# 5V2A_Flyback_converter_Schematic.net
KiCad netlist of a schematic drawn in Altium Designer
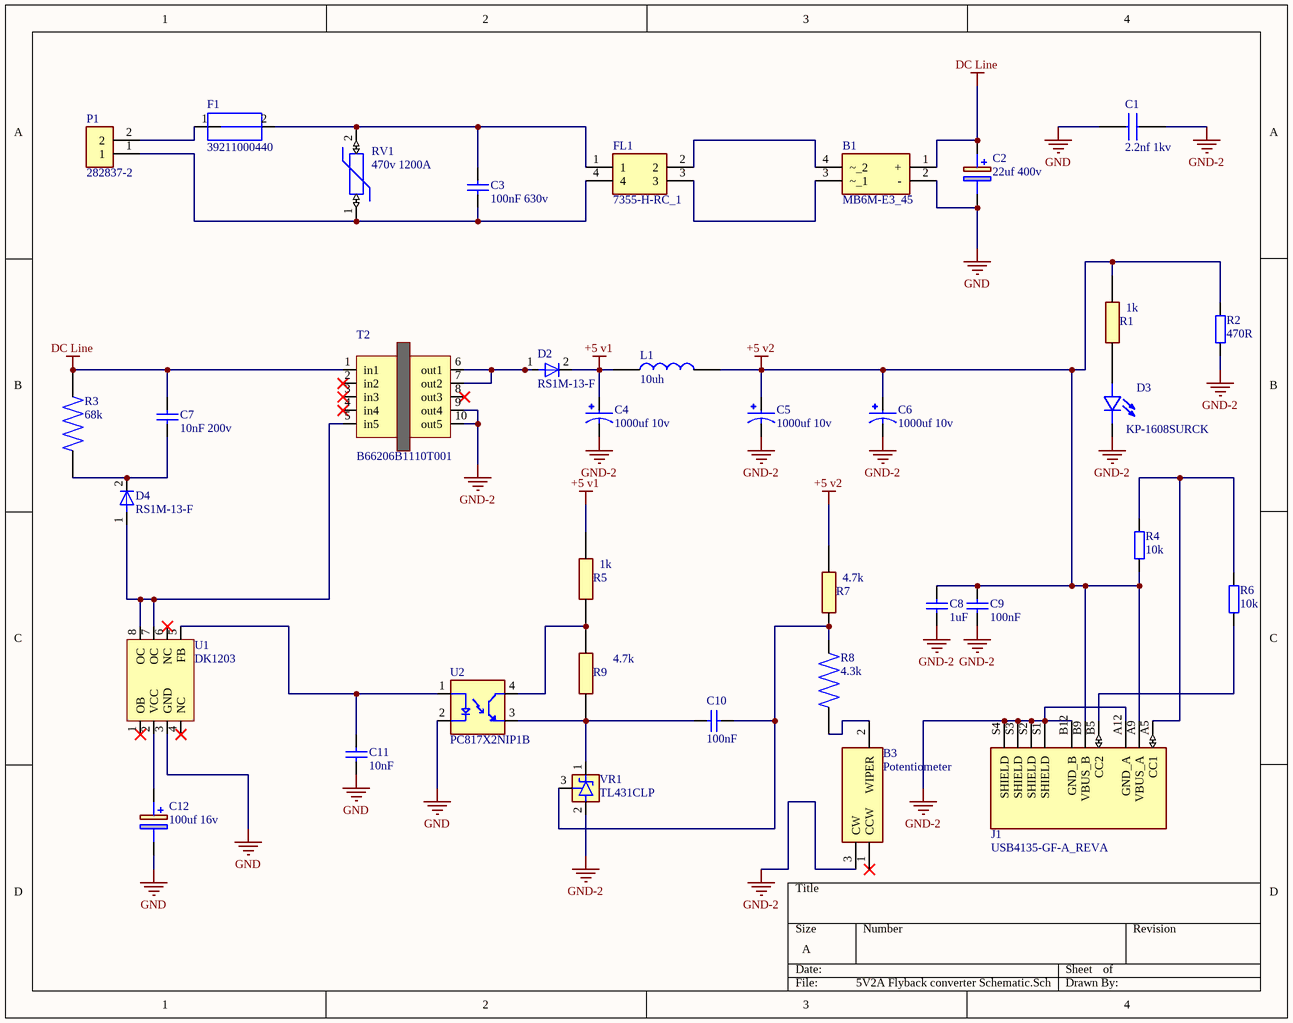
[diagram p0: 5V2A Flyback converter Schematic.SchDoc]

(export (version "E")
  (design (tool "Eeschema 10.0.6"))
  (components
    (comp (ref "B1")
      (value "MB6M-E3_45")
      (footprint "DIP508W74P254L469H270Q4N")
      (description "Diode Rectifier Bridge Single 600V 0.8A Vishay MB6M-E3/45, Bridge Rectifier, 0.8A 600V, 4-Pin MBM")
      (fields
        (field (name "MANUFACTURER_PART_NUMBER") "MB6M-E3/45")
        (field (name "MOUSER PART NUMBER") "625-MB6M-E3")
      )
      (libsource (lib "5V2A Flyback converter Schematic library") (part "MB6M-E3_45"))
    )
    (comp (ref "B3")
      (value "Potentiometer")
      (footprint "3296Y1504LF")
      (description "Trimmer Resistors - Through Hole 3/8\" 500Kohms Sealed Vertical Adjust")
      (fields
        (field (name "MANUFACTURER_PART_NUMBER") "3296Y-1-504LF")
        (field (name "MOUSER PART NUMBER") "652-3296Y-1-504LF")
      )
      (libsource (lib "5V2A Flyback converter Schematic library") (part "Potentiometer"))
    )
    (comp (ref "C1")
      (value "2.2nf 1kv")
      (footprint "CK45B3AD222KYNNA")
      (fields
        (field (name "MANUFACTURER_PART_NUMBER") "CK45-B3AD222KYNNA")
        (field (name "MOUSER PART NUMBER") "810-CK45-B3AD222NNA")
      )
      (libsource (lib "5V2A Flyback converter Schematic library") (part "2.2nf 1kv"))
    )
    (comp (ref "C2")
      (value "22uf 400v")
      (footprint "CAPPRD500W65D1250H2700")
      (description "Aluminium Electrolytic Capacitors - Radial Leaded Al Lytic Cap Radial NHG Series 105C")
      (fields
        (field (name "MANUFACTURER_PART_NUMBER") "ECA-2GHG220")
        (field (name "MOUSER PART NUMBER") "667-ECA-2GHG220")
      )
      (libsource (lib "5V2A Flyback converter Schematic library") (part "22uf"))
    )
    (comp (ref "C3")
      (value "100nF 630v")
      (footprint "WCAP-CSMH_1812_L4.5W3.2H2")
      (fields
        (field (name "MANUFACTURER PART NUMBER") "885342211006")
        (field (name "MANUFACTURER") "Wurth Elektronik")
      )
      (libsource (lib "885342006001_Altium_WCAP-CSMH_rev24a") (part "885342211006"))
    )
    (comp (ref "C4")
      (value "1000uf 10v")
      (footprint "CAP_EEEFN1A102P")
      (description "CAP ALUM 1000UF 20% 10V SMD")
      (fields (field (name "MP") "EEE-FN1A102P") (field (name "MF") "Panasonic Electronic Components"))
      (libsource (lib "EEEFN1A102P") (part "EEEFN1A102P"))
    )
    (comp (ref "C5")
      (value "1000uf 10v")
      (footprint "CAP_EEEFN1A102P")
      (description "CAP ALUM 1000UF 20% 10V SMD")
      (fields (field (name "MP") "EEE-FN1A102P") (field (name "MF") "Panasonic Electronic Components"))
      (libsource (lib "EEEFN1A102P") (part "EEEFN1A102P"))
    )
    (comp (ref "C6")
      (value "1000uf 10v")
      (footprint "CAP_EEEFN1A102P")
      (description "CAP ALUM 1000UF 20% 10V SMD")
      (fields (field (name "MP") "EEE-FN1A102P") (field (name "MF") "Panasonic Electronic Components"))
      (libsource (lib "EEEFN1A102P") (part "EEEFN1A102P"))
    )
    (comp (ref "C7")
      (value "10nF 200v")
      (footprint "WCAP-CSMH_0805_L2W1.25H1.25")
      (fields
        (field (name "MANUFACTURER PART NUMBER") "885342207005")
        (field (name "MANUFACTURER") "Wurth Elektronik")
      )
      (libsource (lib "885342006001_Altium_WCAP-CSMH_rev24a") (part "885342207005"))
    )
    (comp (ref "C8")
      (value "1uF")
      (footprint "WCAP-CSST_0805_L2W1.25H1.25")
      (fields
        (field (name "MANUFACTURER PART NUMBER") "885382207001")
        (field (name "MANUFACTURER") "Wurth Elektronik")
      )
      (libsource (lib "885382206001_Altium_WCAP-CSST_rev24b") (part "885382207001"))
    )
    (comp (ref "C9")
      (value "100nF")
      (footprint "WCAP-CSST_0805_L2W1.25H1.25")
      (fields
        (field (name "MANUFACTURER PART NUMBER") "885382207007")
        (field (name "MANUFACTURER") "Wurth Elektronik")
      )
      (libsource (lib "885382206001_Altium_WCAP-CSST_rev24b") (part "885382207007"))
    )
    (comp (ref "C10")
      (value "100nF")
      (footprint "WCAP-CSST_1206_L3.2W1.6H1.25")
      (fields
        (field (name "MANUFACTURER PART NUMBER") "885382208006")
        (field (name "MANUFACTURER") "Wurth Elektronik")
      )
      (libsource (lib "885382206001_Altium_WCAP-CSST_rev24b") (part "885382208006"))
    )
    (comp (ref "C11")
      (value "10nF")
      (footprint "WCAP-CSST_1206_L3.2W1.6H1.25")
      (fields
        (field (name "MANUFACTURER PART NUMBER") "885382208002")
        (field (name "MANUFACTURER") "Wurth Elektronik")
      )
      (libsource (lib "885382206001_Altium_WCAP-CSST_rev24b") (part "885382208002"))
    )
    (comp (ref "C12")
      (value "100uf 16v")
      (footprint "CAPAE1030X1100N")
      (description "Nichicon 100uF 16 V dc Polymer Aluminium Electrolytic Capacitor, PS Series 2000h 10 Dia. x 7.7mm")
      (fields
        (field (name "MANUFACTURER_PART_NUMBER") "RPS1C101MCN1GS")
        (field (name "MOUSER PART NUMBER") "647-RPS1C101MCN1GS")
      )
      (libsource (lib "5V2A Flyback converter Schematic library") (part "100uf16v"))
    )
    (comp (ref "D2")
      (value "RS1M-13-F")
      (footprint "B360A-13-F")
      (description "Rectifier Diode Switching 1KV 1A 500ns 2-Pin SMA T/R / DIODE GEN PURP 1KV 1A SMA")
      (fields (field (name "MANUFACTURER") "Diodes") (field (name "VOLTAGE") "1kV"))
      (libsource (lib "5V2A Flyback converter Schematic library") (part "RS1M-13-F"))
    )
    (comp (ref "D3")
      (value "KP-1608SURCK")
      (footprint "LED_KP-1608SURCK")
      (description "LED; SMD; 0603; red; 50-150mcd; 1.6x0.8mm; 120Â°; 20mA;")
      (fields (field (name "MF") "Kingbright"))
      (libsource (lib "KP-1608SURCK") (part "KP-1608SURCK"))
    )
    (comp (ref "D4")
      (value "RS1M-13-F")
      (footprint "B360A-13-F")
      (description "Rectifier Diode Switching 1KV 1A 500ns 2-Pin SMA T/R / DIODE GEN PURP 1KV 1A SMA")
      (fields (field (name "MANUFACTURER") "Diodes") (field (name "VOLTAGE") "1kV"))
      (libsource (lib "5V2A Flyback converter Schematic library") (part "RS1M-13-F"))
    )
    (comp (ref "F1")
      (value "39211000440")
      (footprint "Littelfuse 39211000440")
      (description "Fuse Subminiature Slow Blow Acting 1.1A 250V Radial 8.5 X 4 X 8mm Thermoplastic Bulk")
      (fields (field (name "MANUFACTURER") "Littelfuse Wickmann"))
      (libsource (lib "5V2A Flyback converter Schematic library") (part "39211000440"))
    )
    (comp (ref "FL1")
      (value "7355-H-RC_1")
      (footprint "SamacSys:7355HRC")
      (description "Filter")
      (fields (field (name "MANUFACTURER_PART_NUMBER") "7355-H-RC"))
      (libsource (lib "5V2A Flyback converter Schematic library") (part "7355-H-RC_1"))
    )
    (comp (ref "J1")
      (value "USB4135-GF-A_REVA")
      (footprint "GCT_USB4135-GF-A_REVA")
      (fields (field (name "MF") "Global Connector Technology") (field (name "MP") "USB4135GFA"))
      (libsource (lib "USB4135-GF-A_REVA") (part "USB4135-GF-A_REVA"))
    )
    (comp (ref "L1")
      (value "10uh")
      (footprint "INDPM5552X200N")
      (description "Vishay IHLP2020BZ-01 Series Shielded Wire-wound SMD Inductor 10 uH +/-20% 4A Idc")
      (fields
        (field (name "MANUFACTURER_PART_NUMBER") "IHLP2020BZER100M01")
        (field (name "MOUSER PART NUMBER") "70-IHLP2020BZER100M0")
      )
      (libsource (lib "5V2A Flyback converter Schematic library") (part "10uh"))
    )
    (comp (ref "P1")
      (value "282837-2")
      (footprint "TE_282837-2")
      (fields (field (name "MF") "TE Connectivity"))
      (libsource (lib "282837-2") (part "282837-2"))
    )
    (comp (ref "R1")
      (value "1k")
      (footprint "4.7k")
      (fields
        (field (name "MANUFACTURER_PART_NUMBER") "CRCW12064K70FKEA")
        (field (name "MOUSER PART NUMBER") "71-CRCW1206-4.7K-E3")
      )
      (libsource (lib "5V2A Flyback converter Schematic library") (part "4.7k"))
    )
    (comp (ref "R2")
      (value "470R")
      (footprint "RES_0402")
      (description "Resistor SMD 0402")
      (libsource (lib "Schematic-Lib-PhilsLab") (part "RES_0402"))
    )
    (comp (ref "R3")
      (value "68k")
      (footprint "RES_ERA6ARW683V")
      (description "RES 68K OHM 0.05% 1/8W 0805")
      (fields (field (name "MF") "Panasonic") (field (name "MP") "ERA6ARW683V"))
      (libsource (lib "ERA6ARW683V") (part "ERA6ARW683V"))
    )
    (comp (ref "R4")
      (value "10k")
      (footprint "RES_0402")
      (description "Resistor SMD 0402")
      (libsource (lib "Schematic-Lib-PhilsLab") (part "RES_0402"))
    )
    (comp (ref "R5")
      (value "1k")
      (footprint "4.7k")
      (fields
        (field (name "MANUFACTURER_PART_NUMBER") "CRCW12064K70FKEA")
        (field (name "MOUSER PART NUMBER") "71-CRCW1206-4.7K-E3")
      )
      (libsource (lib "5V2A Flyback converter Schematic library") (part "4.7k"))
    )
    (comp (ref "R6")
      (value "10k")
      (footprint "RES_0402")
      (description "Resistor SMD 0402")
      (libsource (lib "Schematic-Lib-PhilsLab") (part "RES_0402"))
    )
    (comp (ref "R7")
      (value "4.7k")
      (footprint "4.7k")
      (fields
        (field (name "MANUFACTURER_PART_NUMBER") "CRCW12064K70FKEA")
        (field (name "MOUSER PART NUMBER") "71-CRCW1206-4.7K-E3")
      )
      (libsource (lib "5V2A Flyback converter Schematic library") (part "4.7k"))
    )
    (comp (ref "R8")
      (value "4.3k")
      (footprint "RES_ERJU03F4301V")
      (description "RES 4.3K OHM 1% 1/10W 0603 SMD")
      (fields (field (name "MF") "Panasonic") (field (name "MP") "ERJ-U03F4301V"))
      (libsource (lib "ERJU03F4301V") (part "ERJU03F4301V"))
    )
    (comp (ref "R9")
      (value "4.7k")
      (footprint "4.7k")
      (fields
        (field (name "MANUFACTURER_PART_NUMBER") "CRCW12064K70FKEA")
        (field (name "MOUSER PART NUMBER") "71-CRCW1206-4.7K-E3")
      )
      (libsource (lib "5V2A Flyback converter Schematic library") (part "4.7k"))
    )
    (comp (ref "RV1")
      (value "470v 1200A")
      (footprint "MOV-07DXXXK(3.9T)")
      (description "47 V 250 A Varistor 1 Circuit Through Hole Disc 7mm")
      (fields (field (name "MF") "Bourns") (field (name "MP") "MOV-07D470K"))
      (libsource (lib "MOV-07D470K") (part "MOV-07D470K"))
    )
    (comp (ref "T2")
      (value "B66206B1110T001")
      (footprint "PCBComponent_1 - duplicate")
      (description "Ferrite Accessories, Planar Cores Accessories(E/ELP), Coil former (E 20/10/6)")
      (fields (field (name "MANUFACTURER") "TDK EPCOS"))
      (libsource (lib "5V2A Flyback converter Schematic library") (part "B66206B1110T001"))
    )
    (comp (ref "U1")
      (value "DK1203")
      (footprint "DK1203 - duplicate")
      (fields
        (field (name "MANUFACTURER") "ON Semiconductor")
        (field (name "MANUFACTURER PART NUMBER") "NCP1203GEVB")
      )
      (libsource (lib "5V2A Flyback converter Schematic library") (part "DK1203"))
    )
    (comp (ref "U2")
      (value "PC817X2NIP1B")
      (footprint "SOIC254P960X420-4N")
      (description "Optocoupler DC-IN 1-CH Transistor DC-OUT 4-Pin DIP SMD T/R")
      (fields (field (name "MF") "Sharp Microelectronics"))
      (libsource (lib "PC817X2NIP1B") (part "PC817X2NIP1B"))
    )
    (comp (ref "VR1")
      (value "TL431CLP")
      (footprint "VREG_TL431CLP")
      (description "Adjustable precision shunt regulator")
      (fields (field (name "MF") "Texas Instruments"))
      (libsource (lib "TL431CLP") (part "TL431CLP"))
    )
  )
  (nets
    (net (code "1") (name "+5 v1") (class "Default")
      (node (ref "C4") (pin "1") (pinfunction "1_1") (pintype "passive"))
      (node (ref "D2") (pin "2") (pinfunction "2_2") (pintype "passive"))
      (node (ref "L1") (pin "1") (pinfunction "1_1") (pintype "passive"))
      (node (ref "R5") (pin "2") (pinfunction "2_2") (pintype "passive"))
    )
    (net (code "2") (name "+5 v2") (class "Default")
      (node (ref "C5") (pin "1") (pinfunction "1_1") (pintype "passive"))
      (node (ref "C6") (pin "1") (pinfunction "1_1") (pintype "passive"))
      (node (ref "C8") (pin "2") (pinfunction "2_2") (pintype "passive"))
      (node (ref "C9") (pin "2") (pinfunction "2_2") (pintype "passive"))
      (node (ref "J1") (pin "A9") (pinfunction "VBUS_A_A9") (pintype "power_in"))
      (node (ref "J1") (pin "B9") (pinfunction "VBUS_B_B9") (pintype "power_in"))
      (node (ref "L1") (pin "2") (pinfunction "2_2") (pintype "passive"))
      (node (ref "R1") (pin "2") (pinfunction "2_2") (pintype "passive"))
      (node (ref "R2") (pin "2") (pinfunction "2_2") (pintype "passive"))
      (node (ref "R4") (pin "1") (pinfunction "1_1") (pintype "passive"))
      (node (ref "R7") (pin "2") (pinfunction "2_2") (pintype "passive"))
    )
    (net (code "3") (name "DC Line") (class "Default")
      (node (ref "B1") (pin "1") (pinfunction "+_1") (pintype "passive"))
      (node (ref "C2") (pin "1") (pinfunction "+_1") (pintype "passive"))
      (node (ref "C7") (pin "2") (pinfunction "2_2") (pintype "passive"))
      (node (ref "R3") (pin "2") (pinfunction "2_2") (pintype "passive"))
      (node (ref "T2") (pin "1") (pinfunction "in1_1") (pintype "passive"))
    )
    (net (code "4") (name "GND") (class "Default")
      (node (ref "B1") (pin "2") (pinfunction "-_2") (pintype "passive"))
      (node (ref "C1") (pin "1") (pinfunction "1_1") (pintype "passive"))
      (node (ref "C11") (pin "1") (pinfunction "1_1") (pintype "passive"))
      (node (ref "C12") (pin "2") (pinfunction "-_2") (pintype "passive"))
      (node (ref "C2") (pin "2") (pinfunction "-_2") (pintype "passive"))
      (node (ref "U1") (pin "3") (pinfunction "GND_3") (pintype "passive"))
      (node (ref "U2") (pin "2") (pinfunction "C_2") (pintype "passive"))
    )
    (net (code "5") (name "GND-2") (class "Default")
      (node (ref "B3") (pin "3") (pinfunction "CW_3") (pintype "passive"))
      (node (ref "C1") (pin "2") (pinfunction "2_2") (pintype "passive"))
      (node (ref "C4") (pin "2") (pinfunction "2_2") (pintype "passive"))
      (node (ref "C5") (pin "2") (pinfunction "2_2") (pintype "passive"))
      (node (ref "C6") (pin "2") (pinfunction "2_2") (pintype "passive"))
      (node (ref "C8") (pin "1") (pinfunction "1_1") (pintype "passive"))
      (node (ref "C9") (pin "1") (pinfunction "1_1") (pintype "passive"))
      (node (ref "D3") (pin "2") (pinfunction "C_2") (pintype "passive"))
      (node (ref "J1") (pin "A12") (pinfunction "GND_A_A12") (pintype "power_in"))
      (node (ref "J1") (pin "B12") (pinfunction "GND_B_B12") (pintype "power_in"))
      (node (ref "J1") (pin "S1") (pinfunction "SHIELD_S1") (pintype "passive"))
      (node (ref "J1") (pin "S2") (pinfunction "SHIELD_S2") (pintype "passive"))
      (node (ref "J1") (pin "S3") (pinfunction "SHIELD_S3") (pintype "passive"))
      (node (ref "J1") (pin "S4") (pinfunction "SHIELD_S4") (pintype "passive"))
      (node (ref "R2") (pin "1") (pinfunction "1_1") (pintype "passive"))
      (node (ref "T2") (pin "10") (pinfunction "out5_10") (pintype "passive"))
      (node (ref "T2") (pin "9") (pinfunction "out4_9") (pintype "passive"))
      (node (ref "VR1") (pin "2") (pinfunction "ANODE_2") (pintype "passive"))
    )
    (net (code "6") (name "Net-(B1-~_1)") (class "Default")
      (node (ref "B1") (pin "3") (pinfunction "~_1_3") (pintype "passive"))
      (node (ref "FL1") (pin "3") (pinfunction "3_3") (pintype "passive"))
    )
    (net (code "7") (name "Net-(B1-~_2)") (class "Default")
      (node (ref "B1") (pin "4") (pinfunction "~_2_4") (pintype "passive"))
      (node (ref "FL1") (pin "2") (pinfunction "2_2") (pintype "passive"))
    )
    (net (code "8") (name "Net-(B3-WIPER)") (class "Default")
      (node (ref "B3") (pin "2") (pinfunction "WIPER_2") (pintype "passive"))
      (node (ref "R8") (pin "1") (pinfunction "1_1") (pintype "passive"))
    )
    (net (code "9") (name "Net-(C3-Pad1)") (class "Default")
      (node (ref "C3") (pin "1") (pinfunction "1_1") (pintype "passive"))
      (node (ref "FL1") (pin "4") (pinfunction "4_4") (pintype "passive"))
      (node (ref "P1") (pin "1") (pinfunction "1_1") (pintype "passive"))
      (node (ref "RV1") (pin "1") (pinfunction "1_1") (pintype "bidirectional"))
    )
    (net (code "10") (name "Net-(C3-Pad2)") (class "Default")
      (node (ref "C3") (pin "2") (pinfunction "2_2") (pintype "passive"))
      (node (ref "F1") (pin "2") (pinfunction "2_2") (pintype "passive"))
      (node (ref "FL1") (pin "1") (pinfunction "1_1") (pintype "passive"))
      (node (ref "RV1") (pin "2") (pinfunction "2_2") (pintype "bidirectional"))
    )
    (net (code "11") (name "Net-(C7-Pad1)") (class "Default")
      (node (ref "C7") (pin "1") (pinfunction "1_1") (pintype "passive"))
      (node (ref "D4") (pin "2") (pinfunction "2_2") (pintype "passive"))
      (node (ref "R3") (pin "1") (pinfunction "1_1") (pintype "passive"))
    )
    (net (code "12") (name "Net-(C12-+)") (class "Default")
      (node (ref "C12") (pin "1") (pinfunction "+_1") (pintype "passive"))
      (node (ref "U1") (pin "2") (pinfunction "VCC_2") (pintype "passive"))
    )
    (net (code "13") (name "Net-(D3-A)") (class "Default")
      (node (ref "D3") (pin "1") (pinfunction "A_1") (pintype "passive"))
      (node (ref "R1") (pin "1") (pinfunction "1_1") (pintype "passive"))
    )
    (net (code "14") (name "Net-(F1-Pad1)") (class "Default")
      (node (ref "F1") (pin "1") (pinfunction "1_1") (pintype "passive"))
      (node (ref "P1") (pin "2") (pinfunction "2_2") (pintype "passive"))
    )
    (net (code "15") (name "Net-(J1-CC1)") (class "Default")
      (node (ref "J1") (pin "A5") (pinfunction "CC1_A5") (pintype "bidirectional"))
      (node (ref "R4") (pin "2") (pinfunction "2_2") (pintype "passive"))
      (node (ref "R6") (pin "2") (pinfunction "2_2") (pintype "passive"))
    )
    (net (code "16") (name "Net-(J1-CC2)") (class "Default")
      (node (ref "J1") (pin "B5") (pinfunction "CC2_B5") (pintype "bidirectional"))
      (node (ref "R6") (pin "1") (pinfunction "1_1") (pintype "passive"))
    )
    (net (code "17") (name "Net-(T2-in5)") (class "Default")
      (node (ref "D4") (pin "1") (pinfunction "1_1") (pintype "passive"))
      (node (ref "T2") (pin "5") (pinfunction "in5_5") (pintype "passive"))
      (node (ref "U1") (pin "7") (pinfunction "OC_7") (pintype "passive"))
      (node (ref "U1") (pin "8") (pinfunction "OC_8") (pintype "passive"))
    )
    (net (code "18") (name "Net-(T2-out1)") (class "Default")
      (node (ref "D2") (pin "1") (pinfunction "1_1") (pintype "passive"))
      (node (ref "T2") (pin "6") (pinfunction "out1_6") (pintype "passive"))
      (node (ref "T2") (pin "7") (pinfunction "out2_7") (pintype "passive"))
    )
    (net (code "19") (name "Net-(U1-FB)") (class "Default")
      (node (ref "C11") (pin "2") (pinfunction "2_2") (pintype "passive"))
      (node (ref "U1") (pin "5") (pinfunction "FB_5") (pintype "passive"))
      (node (ref "U2") (pin "1") (pinfunction "A_1") (pintype "passive"))
    )
    (net (code "20") (name "Net-(U2-CT)") (class "Default")
      (node (ref "R5") (pin "1") (pinfunction "1_1") (pintype "passive"))
      (node (ref "R9") (pin "2") (pinfunction "2_2") (pintype "passive"))
      (node (ref "U2") (pin "4") (pinfunction "CT_4") (pintype "passive"))
    )
    (net (code "21") (name "Net-(U2-ET)") (class "Default")
      (node (ref "C10") (pin "1") (pinfunction "1_1") (pintype "passive"))
      (node (ref "R9") (pin "1") (pinfunction "1_1") (pintype "passive"))
      (node (ref "U2") (pin "3") (pinfunction "ET_3") (pintype "passive"))
      (node (ref "VR1") (pin "1") (pinfunction "CATHODE_1") (pintype "passive"))
    )
    (net (code "22") (name "Net-(VR1-REF)") (class "Default")
      (node (ref "C10") (pin "2") (pinfunction "2_2") (pintype "passive"))
      (node (ref "R7") (pin "1") (pinfunction "1_1") (pintype "passive"))
      (node (ref "R8") (pin "2") (pinfunction "2_2") (pintype "passive"))
      (node (ref "VR1") (pin "3") (pinfunction "REF_3") (pintype "passive"))
    )
    (net (code "23") (name "unconnected-(B3-CCW-Pad1)") (class "Default")
      (node (ref "B3") (pin "1") (pinfunction "CCW_1") (pintype "passive+no_connect"))
    )
    (net (code "24") (name "unconnected-(T2-in2-Pad2)") (class "Default")
      (node (ref "T2") (pin "2") (pinfunction "in2_2") (pintype "passive+no_connect"))
    )
    (net (code "25") (name "unconnected-(T2-in3-Pad3)") (class "Default")
      (node (ref "T2") (pin "3") (pinfunction "in3_3") (pintype "passive+no_connect"))
    )
    (net (code "26") (name "unconnected-(T2-in4-Pad4)") (class "Default")
      (node (ref "T2") (pin "4") (pinfunction "in4_4") (pintype "passive+no_connect"))
    )
    (net (code "27") (name "unconnected-(T2-out3-Pad8)") (class "Default")
      (node (ref "T2") (pin "8") (pinfunction "out3_8") (pintype "passive+no_connect"))
    )
    (net (code "28") (name "unconnected-(U1-NC-Pad4)") (class "Default")
      (node (ref "U1") (pin "4") (pinfunction "NC_4") (pintype "passive+no_connect"))
    )
    (net (code "29") (name "unconnected-(U1-NC-Pad6)") (class "Default")
      (node (ref "U1") (pin "6") (pinfunction "NC_6") (pintype "passive+no_connect"))
    )
    (net (code "30") (name "unconnected-(U1-OB-Pad1)") (class "Default")
      (node (ref "U1") (pin "1") (pinfunction "OB_1") (pintype "passive+no_connect"))
    )
  )
)
